# DLP.net
KiCad netlist of a schematic drawn in Altium Designer
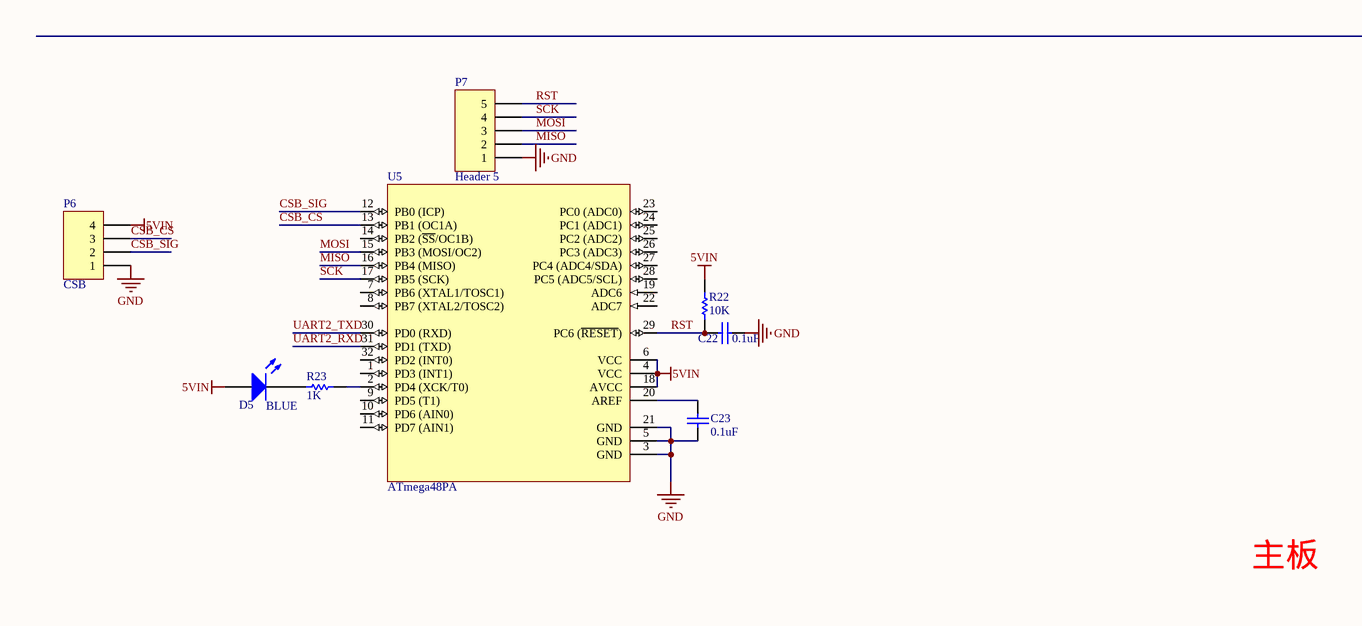
[diagram p0: DLP.SchDoc, top left]
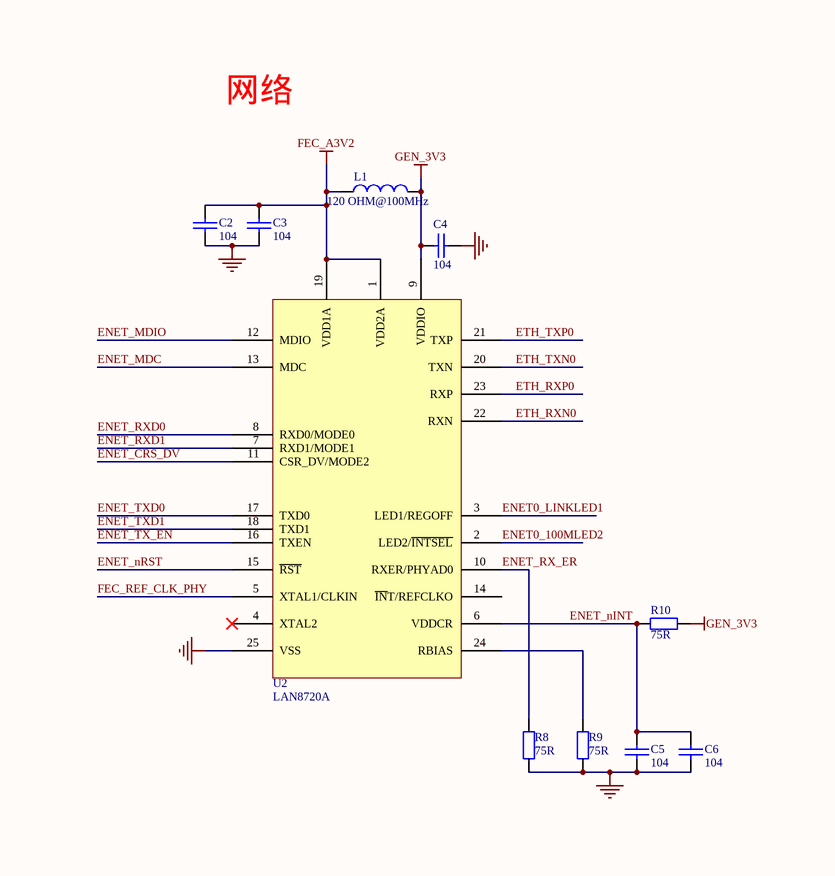
[diagram p1: DLP.SchDoc, top right]
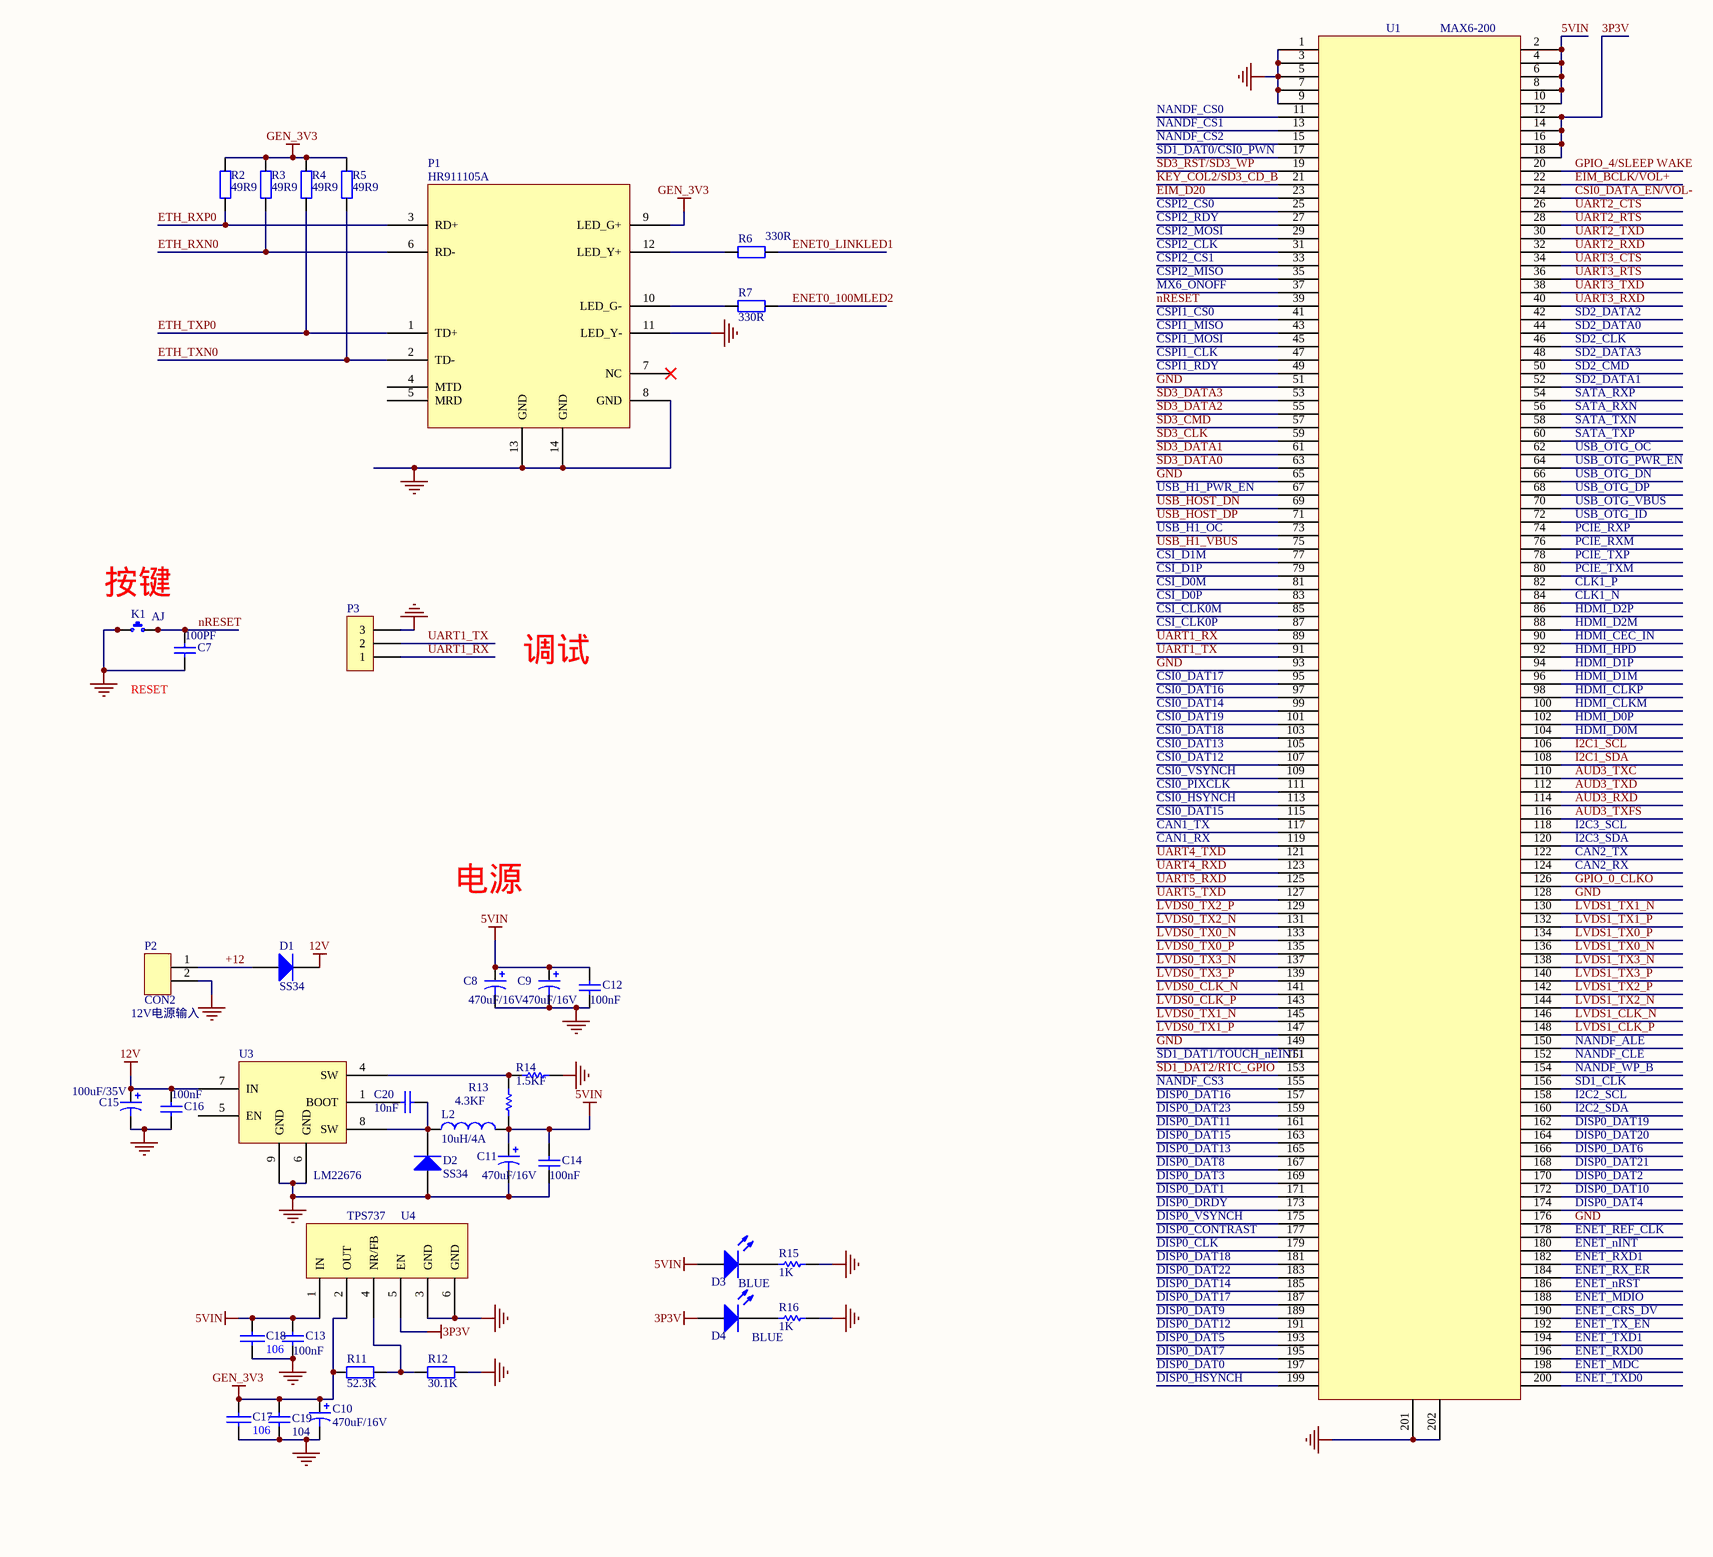
[diagram p2: DLP.SchDoc, bottom left]
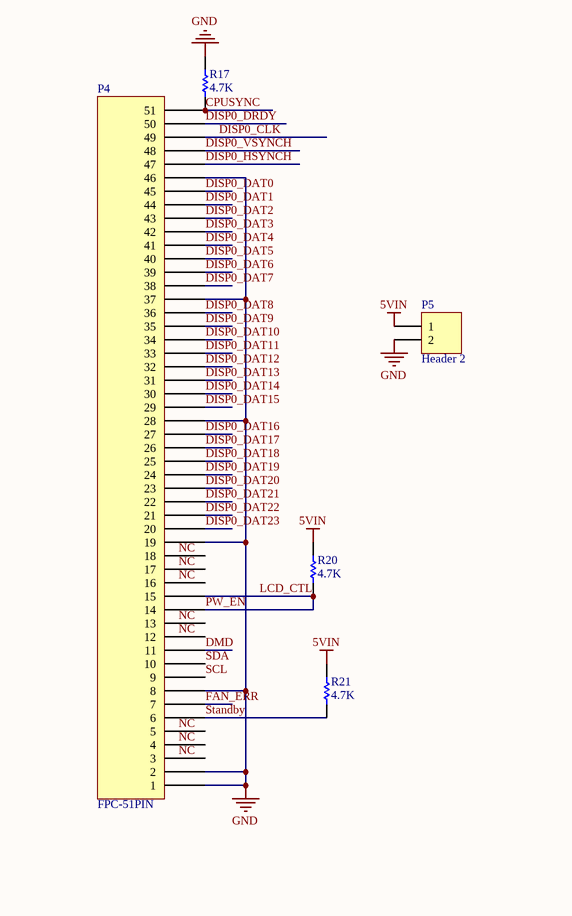
[diagram p3: DLP.SchDoc, bottom right]

(export (version "E")
  (design (tool "Eeschema 10.0.6"))
  (components
    (comp (ref "C2") (value "104") (footprint "0603C") (libsource (lib "*") (part "CAP")))
    (comp (ref "C3") (value "104") (footprint "0603C") (libsource (lib "*") (part "CAP")))
    (comp (ref "C4") (value "104") (footprint "0603C") (libsource (lib "*") (part "CAP")))
    (comp (ref "C5") (value "104") (footprint "0603C") (libsource (lib "*") (part "CAP")))
    (comp (ref "C6") (value "104") (footprint "0603C") (libsource (lib "*") (part "CAP")))
    (comp (ref "C7")
      (value "100PF")
      (footprint "0603C")
      (description "Capacitor")
      (libsource (lib "*") (part "Cap"))
    )
    (comp (ref "C8")
      (value "470uF/16V")
      (footprint "C8")
      (description "Polarized Capacitor (Radial)")
      (libsource (lib "*") (part "Cap Pol1"))
    )
    (comp (ref "C9")
      (value "470uF/16V")
      (footprint "C8")
      (description "Polarized Capacitor (Radial)")
      (libsource (lib "*") (part "Cap Pol1"))
    )
    (comp (ref "C10")
      (value "470uF/16V")
      (footprint "C8")
      (description "Polarized Capacitor (Radial)")
      (libsource (lib "*") (part "Cap Pol1"))
    )
    (comp (ref "C11")
      (value "470uF/16V")
      (footprint "C8")
      (description "Polarized Capacitor (Radial)")
      (libsource (lib "*") (part "Cap Pol1"))
    )
    (comp (ref "C12")
      (value "100nF")
      (footprint "0603C")
      (description "Capacitor")
      (libsource (lib "*") (part "Cap"))
    )
    (comp (ref "C13")
      (value "100nF")
      (footprint "0603C")
      (description "Capacitor")
      (libsource (lib "*") (part "Cap"))
    )
    (comp (ref "C14")
      (value "100nF")
      (footprint "0603C")
      (description "Capacitor")
      (libsource (lib "*") (part "Cap"))
    )
    (comp (ref "C15")
      (value "100uF/35V")
      (footprint "C8")
      (description "Polarized Capacitor (Radial)")
      (libsource (lib "*") (part "Cap Pol1"))
    )
    (comp (ref "C16")
      (value "100nF")
      (footprint "0603C")
      (description "Capacitor")
      (libsource (lib "*") (part "Cap"))
    )
    (comp (ref "C17") (value "106") (footprint "0603C") (libsource (lib "") (part "CAP_1")))
    (comp (ref "C18") (value "106") (footprint "0603C") (libsource (lib "") (part "CAP_1")))
    (comp (ref "C19")
      (value "104")
      (footprint "0603C")
      (fields (field (name "PUBLISHER") "Altium Limited"))
      (libsource (lib "*") (part "Cap"))
    )
    (comp (ref "C20")
      (value "10nF")
      (footprint "0603")
      (description "Capacitor")
      (libsource (lib "*") (part "Cap"))
    )
    (comp (ref "C22")
      (value "0.1uF")
      (footprint "0603")
      (description "Capacitor")
      (fields (field (name "Comment") "Cap") (field (name "PUBLISHER") "Altium Limited"))
      (libsource (lib "Miscellaneous Devices") (part "Cap"))
    )
    (comp (ref "C23")
      (value "0.1uF")
      (footprint "0603")
      (description "Capacitor")
      (fields (field (name "Comment") "Cap") (field (name "PUBLISHER") "Altium Limited"))
      (libsource (lib "Miscellaneous Devices") (part "Cap"))
    )
    (comp (ref "D1")
      (value "SS34")
      (footprint "SMB")
      (description "3 Amp Medium Power Silicon Rectifier Diode")
      (libsource (lib "*") (part "Diode 1N5408"))
    )
    (comp (ref "D2")
      (value "SS34")
      (footprint "SMB")
      (description "3 Amp Medium Power Silicon Rectifier Diode")
      (libsource (lib "*") (part "Diode 1N5408"))
    )
    (comp (ref "D3")
      (value "BLUE")
      (footprint "0603D")
      (description "Typical RED, GREEN, YELLOW, AMBER GaAs LED")
      (libsource (lib "*") (part "LED2"))
    )
    (comp (ref "D4")
      (value "BLUE")
      (footprint "0603D")
      (description "Typical RED, GREEN, YELLOW, AMBER GaAs LED")
      (libsource (lib "*") (part "LED2"))
    )
    (comp (ref "D5")
      (value "BLUE")
      (footprint "0603-LED")
      (description "Typical RED, GREEN, YELLOW, AMBER GaAs LED")
      (libsource (lib "*") (part "LED2"))
    )
    (comp (ref "K1") (value "AJ") (footprint "4*4*1.5") (libsource (lib "*") (part "KEY_1")))
    (comp (ref "L1")
      (value "120 OHM@100MHz")
      (footprint "0603")
      (description "Inductor")
      (libsource (lib "*") (part "Inductor"))
    )
    (comp (ref "L2")
      (value "10uH/4A")
      (footprint "8040")
      (description "Inductor")
      (libsource (lib "*") (part "Inductor"))
    )
    (comp (ref "P1") (value "HR911105A") (footprint "HR911105A") (libsource (lib "*") (part "HR911105A")))
    (comp (ref "P2") (value "CON2") (footprint "XH2.54-2P") (libsource (lib "*") (part "CON2")))
    (comp (ref "P3")
      (value "~")
      (footprint "HDR1X3")
      (description "Connector")
      (libsource (lib "*") (part "CON3"))
    )
    (comp (ref "P4")
      (value "FPC-51PIN")
      (footprint "FH26-51S-0.3SHW")
      (libsource (lib "TANK") (part "FPC-51PIN"))
    )
    (comp (ref "P5")
      (value "Header 2")
      (footprint "PH2.0-2P")
      (description "Header, 2-Pin")
      (fields (field (name "PUBLISHER") "Altium Limited"))
      (libsource (lib "Miscellaneous Connectors") (part "Header 2"))
    )
    (comp (ref "P6")
      (value "CSB")
      (footprint "HDR1X4")
      (description "Header, 4-Pin")
      (fields (field (name "PUBLISHER") "Altium Limited"))
      (libsource (lib "Miscellaneous Connectors") (part "Header 4"))
    )
    (comp (ref "P7")
      (value "Header 5")
      (footprint "HDR1X5")
      (description "Header, 5-Pin")
      (fields (field (name "PUBLISHER") "Altium Limited"))
      (libsource (lib "Miscellaneous Connectors") (part "Header 5"))
    )
    (comp (ref "R2") (value "49R9") (footprint "0603R") (libsource (lib "*") (part "RES")))
    (comp (ref "R3") (value "49R9") (footprint "0603R") (libsource (lib "*") (part "RES")))
    (comp (ref "R4") (value "49R9") (footprint "0603R") (libsource (lib "*") (part "RES")))
    (comp (ref "R5") (value "49R9") (footprint "0603") (libsource (lib "*") (part "RES")))
    (comp (ref "R6") (value "330R") (footprint "0603R") (libsource (lib "*") (part "RES")))
    (comp (ref "R7") (value "330R") (footprint "0603R") (libsource (lib "*") (part "RES")))
    (comp (ref "R8") (value "75R") (footprint "0603R") (libsource (lib "*") (part "RES")))
    (comp (ref "R9") (value "75R") (footprint "0603R") (libsource (lib "*") (part "RES")))
    (comp (ref "R10") (value "75R") (footprint "0603R") (libsource (lib "*") (part "RES")))
    (comp (ref "R11")
      (value "52.3K")
      (footprint "0603R")
      (description "Resistor")
      (fields (field (name "PUBLISHER") "Altium Limited"))
      (libsource (lib "*") (part "Res2"))
    )
    (comp (ref "R12")
      (value "30.1K")
      (footprint "0603R")
      (description "Resistor")
      (fields (field (name "PUBLISHER") "Altium Limited"))
      (libsource (lib "") (part "Res2_1"))
    )
    (comp (ref "R13")
      (value "4.3KF")
      (footprint "0603R")
      (description "Resistor")
      (libsource (lib "*") (part "Res1"))
    )
    (comp (ref "R14")
      (value "1.5KF")
      (footprint "0603R")
      (description "Resistor")
      (libsource (lib "*") (part "Res1"))
    )
    (comp (ref "R15")
      (value "1K")
      (footprint "0603R")
      (description "Resistor")
      (libsource (lib "*") (part "Res1"))
    )
    (comp (ref "R16")
      (value "1K")
      (footprint "0603R")
      (description "Resistor")
      (libsource (lib "*") (part "Res1"))
    )
    (comp (ref "R17")
      (value "4.7K")
      (footprint "0603")
      (description "Resistor")
      (fields (field (name "Comment") "Res1") (field (name "PUBLISHER") "Altium Limited"))
      (libsource (lib "Miscellaneous Devices") (part "Res1"))
    )
    (comp (ref "R20")
      (value "4.7K")
      (footprint "0603")
      (description "Resistor")
      (fields (field (name "Comment") "Res1") (field (name "PUBLISHER") "Altium Limited"))
      (libsource (lib "Miscellaneous Devices") (part "Res1"))
    )
    (comp (ref "R21")
      (value "4.7K")
      (footprint "0603")
      (description "Resistor")
      (fields (field (name "Comment") "Res1") (field (name "PUBLISHER") "Altium Limited"))
      (libsource (lib "Miscellaneous Devices") (part "Res1"))
    )
    (comp (ref "R22")
      (value "10K")
      (footprint "0603")
      (description "Resistor")
      (fields (field (name "Comment") "Res1") (field (name "PUBLISHER") "Altium Limited"))
      (libsource (lib "Miscellaneous Devices") (part "Res1"))
    )
    (comp (ref "R23")
      (value "1K")
      (footprint "0603")
      (description "Resistor")
      (libsource (lib "*") (part "Res1"))
    )
    (comp (ref "U1") (value "MAX6-200") (footprint "SO-DIMM 200") (libsource (lib "*") (part "MAX6-200")))
    (comp (ref "U2") (value "LAN8720A") (footprint "QFN24_4X4MM") (libsource (lib "*") (part "LAN8720A")))
    (comp (ref "U3") (value "LM22676") (footprint "SO-8HP") (libsource (lib "*") (part "LM22676")))
    (comp (ref "U4") (value "TPS737") (footprint "SOT223-6") (libsource (lib "*") (part "TPS737")))
    (comp (ref "U5")
      (value "ATmega48PA")
      (footprint "32A_M")
      (description "8-Bit AVR Microcontroller with 8K Bytes of In-System Programmable Flash Memory")
      (fields (field (name "PUBLISHER") "Altium Limited"))
      (libsource (lib "Atmel Microcontroller 8-Bit AVR") (part "ATmega8-16AC"))
    )
  )
  (nets
    (net (code "1") (name "/+12") (class "Default")
      (node (ref "D1") (pin "1") (pinfunction "A_1") (pintype "passive"))
      (node (ref "P2") (pin "1") (pinfunction "1_1") (pintype "passive"))
    )
    (net (code "2") (name "/AUD3_RXD") (class "Default") (node (ref "U1") (pin "114") (pintype "passive")))
    (net (code "3") (name "/AUD3_TXC") (class "Default") (node (ref "U1") (pin "110") (pintype "passive")))
    (net (code "4") (name "/AUD3_TXD") (class "Default") (node (ref "U1") (pin "112") (pintype "passive")))
    (net (code "5") (name "/AUD3_TXFS") (class "Default") (node (ref "U1") (pin "116") (pintype "passive")))
    (net (code "6") (name "/CAN1_RX") (class "Default") (node (ref "U1") (pin "119") (pintype "passive")))
    (net (code "7") (name "/CAN1_TX") (class "Default") (node (ref "U1") (pin "117") (pintype "passive")))
    (net (code "8") (name "/CAN2_RX") (class "Default") (node (ref "U1") (pin "124") (pintype "passive")))
    (net (code "9") (name "/CAN2_TX") (class "Default") (node (ref "U1") (pin "122") (pintype "passive")))
    (net (code "10") (name "/CLK1_N") (class "Default") (node (ref "U1") (pin "84") (pintype "passive")))
    (net (code "11") (name "/CLK1_P") (class "Default") (node (ref "U1") (pin "82") (pintype "passive")))
    (net (code "12") (name "/CPUSYNC") (class "Default")
      (node (ref "P4") (pin "51") (pinfunction "51_51") (pintype "passive"))
      (node (ref "R17") (pin "2") (pinfunction "2_2") (pintype "passive"))
    )
    (net (code "13") (name "/CSB_CS") (class "Default")
      (node (ref "P6") (pin "3") (pinfunction "3_3") (pintype "passive"))
      (node (ref "U5") (pin "13") (pinfunction "PB1_(OC1A)_13") (pintype "bidirectional"))
    )
    (net (code "14") (name "/CSB_SIG") (class "Default")
      (node (ref "P6") (pin "2") (pinfunction "2_2") (pintype "passive"))
      (node (ref "U5") (pin "12") (pinfunction "PB0_(ICP)_12") (pintype "bidirectional"))
    )
    (net (code "15") (name "/CSI0_DAT12") (class "Default") (node (ref "U1") (pin "107") (pintype "passive")))
    (net (code "16") (name "/CSI0_DAT13") (class "Default") (node (ref "U1") (pin "105") (pintype "passive")))
    (net (code "17") (name "/CSI0_DAT14") (class "Default") (node (ref "U1") (pin "99") (pintype "passive")))
    (net (code "18") (name "/CSI0_DAT15") (class "Default") (node (ref "U1") (pin "115") (pintype "passive")))
    (net (code "19") (name "/CSI0_DAT16") (class "Default") (node (ref "U1") (pin "97") (pintype "passive")))
    (net (code "20") (name "/CSI0_DAT17") (class "Default") (node (ref "U1") (pin "95") (pintype "passive")))
    (net (code "21") (name "/CSI0_DAT18") (class "Default") (node (ref "U1") (pin "103") (pintype "passive")))
    (net (code "22") (name "/CSI0_DAT19") (class "Default") (node (ref "U1") (pin "101") (pintype "passive")))
    (net (code "23") (name "/CSI0_DATA_EN{slash}VOL-") (class "Default")
      (node (ref "U1") (pin "24") (pintype "passive"))
    )
    (net (code "24") (name "/CSI0_HSYNCH") (class "Default")
      (node (ref "U1") (pin "113") (pintype "passive"))
    )
    (net (code "25") (name "/CSI0_PIXCLK") (class "Default")
      (node (ref "U1") (pin "111") (pintype "passive"))
    )
    (net (code "26") (name "/CSI0_VSYNCH") (class "Default")
      (node (ref "U1") (pin "109") (pintype "passive"))
    )
    (net (code "27") (name "/CSI_CLK0M") (class "Default") (node (ref "U1") (pin "85") (pintype "passive")))
    (net (code "28") (name "/CSI_CLK0P") (class "Default") (node (ref "U1") (pin "87") (pintype "passive")))
    (net (code "29") (name "/CSI_D0M") (class "Default") (node (ref "U1") (pin "81") (pintype "passive")))
    (net (code "30") (name "/CSI_D0P") (class "Default") (node (ref "U1") (pin "83") (pintype "passive")))
    (net (code "31") (name "/CSI_D1M") (class "Default") (node (ref "U1") (pin "77") (pintype "passive")))
    (net (code "32") (name "/CSI_D1P") (class "Default") (node (ref "U1") (pin "79") (pintype "passive")))
    (net (code "33") (name "/CSPI1_CLK") (class "Default") (node (ref "U1") (pin "47") (pintype "passive")))
    (net (code "34") (name "/CSPI1_CS0") (class "Default") (node (ref "U1") (pin "41") (pintype "passive")))
    (net (code "35") (name "/CSPI1_MISO") (class "Default") (node (ref "U1") (pin "43") (pintype "passive")))
    (net (code "36") (name "/CSPI1_MOSI") (class "Default") (node (ref "U1") (pin "45") (pintype "passive")))
    (net (code "37") (name "/CSPI1_RDY") (class "Default") (node (ref "U1") (pin "49") (pintype "passive")))
    (net (code "38") (name "/CSPI2_CLK") (class "Default") (node (ref "U1") (pin "31") (pintype "passive")))
    (net (code "39") (name "/CSPI2_CS0") (class "Default") (node (ref "U1") (pin "25") (pintype "passive")))
    (net (code "40") (name "/CSPI2_CS1") (class "Default") (node (ref "U1") (pin "33") (pintype "passive")))
    (net (code "41") (name "/CSPI2_MISO") (class "Default") (node (ref "U1") (pin "35") (pintype "passive")))
    (net (code "42") (name "/CSPI2_MOSI") (class "Default") (node (ref "U1") (pin "29") (pintype "passive")))
    (net (code "43") (name "/CSPI2_RDY") (class "Default") (node (ref "U1") (pin "27") (pintype "passive")))
    (net (code "44") (name "/DISP0_CLK") (class "Default")
      (node (ref "P4") (pin "49") (pinfunction "49_49") (pintype "passive"))
      (node (ref "U1") (pin "179") (pintype "passive"))
    )
    (net (code "45") (name "/DISP0_CONTRAST") (class "Default")
      (node (ref "U1") (pin "177") (pintype "passive"))
    )
    (net (code "46") (name "/DISP0_DAT0") (class "Default")
      (node (ref "P4") (pin "45") (pinfunction "45_45") (pintype "passive"))
      (node (ref "U1") (pin "197") (pintype "passive"))
    )
    (net (code "47") (name "/DISP0_DAT1") (class "Default")
      (node (ref "P4") (pin "44") (pinfunction "44_44") (pintype "passive"))
      (node (ref "U1") (pin "171") (pintype "passive"))
    )
    (net (code "48") (name "/DISP0_DAT2") (class "Default")
      (node (ref "P4") (pin "43") (pinfunction "43_43") (pintype "passive"))
      (node (ref "U1") (pin "170") (pintype "passive"))
    )
    (net (code "49") (name "/DISP0_DAT3") (class "Default")
      (node (ref "P4") (pin "42") (pinfunction "42_42") (pintype "passive"))
      (node (ref "U1") (pin "169") (pintype "passive"))
    )
    (net (code "50") (name "/DISP0_DAT4") (class "Default")
      (node (ref "P4") (pin "41") (pinfunction "41_41") (pintype "passive"))
      (node (ref "U1") (pin "174") (pintype "passive"))
    )
    (net (code "51") (name "/DISP0_DAT5") (class "Default")
      (node (ref "P4") (pin "40") (pinfunction "40_40") (pintype "passive"))
      (node (ref "U1") (pin "193") (pintype "passive"))
    )
    (net (code "52") (name "/DISP0_DAT6") (class "Default")
      (node (ref "P4") (pin "39") (pinfunction "39_39") (pintype "passive"))
      (node (ref "U1") (pin "166") (pintype "passive"))
    )
    (net (code "53") (name "/DISP0_DAT7") (class "Default")
      (node (ref "P4") (pin "38") (pinfunction "38_38") (pintype "passive"))
      (node (ref "U1") (pin "195") (pintype "passive"))
    )
    (net (code "54") (name "/DISP0_DAT8") (class "Default")
      (node (ref "P4") (pin "36") (pinfunction "36_36") (pintype "passive"))
      (node (ref "U1") (pin "167") (pintype "passive"))
    )
    (net (code "55") (name "/DISP0_DAT9") (class "Default")
      (node (ref "P4") (pin "35") (pinfunction "35_35") (pintype "passive"))
      (node (ref "U1") (pin "189") (pintype "passive"))
    )
    (net (code "56") (name "/DISP0_DAT10") (class "Default")
      (node (ref "P4") (pin "34") (pinfunction "34_34") (pintype "passive"))
      (node (ref "U1") (pin "172") (pintype "passive"))
    )
    (net (code "57") (name "/DISP0_DAT11") (class "Default")
      (node (ref "P4") (pin "33") (pinfunction "33_33") (pintype "passive"))
      (node (ref "U1") (pin "161") (pintype "passive"))
    )
    (net (code "58") (name "/DISP0_DAT12") (class "Default")
      (node (ref "P4") (pin "32") (pinfunction "32_32") (pintype "passive"))
      (node (ref "U1") (pin "191") (pintype "passive"))
    )
    (net (code "59") (name "/DISP0_DAT13") (class "Default")
      (node (ref "P4") (pin "31") (pinfunction "31_31") (pintype "passive"))
      (node (ref "U1") (pin "165") (pintype "passive"))
    )
    (net (code "60") (name "/DISP0_DAT14") (class "Default")
      (node (ref "P4") (pin "30") (pinfunction "30_30") (pintype "passive"))
      (node (ref "U1") (pin "185") (pintype "passive"))
    )
    (net (code "61") (name "/DISP0_DAT15") (class "Default")
      (node (ref "P4") (pin "29") (pinfunction "29_29") (pintype "passive"))
      (node (ref "U1") (pin "163") (pintype "passive"))
    )
    (net (code "62") (name "/DISP0_DAT16") (class "Default")
      (node (ref "P4") (pin "27") (pinfunction "27_27") (pintype "passive"))
      (node (ref "U1") (pin "157") (pintype "passive"))
    )
    (net (code "63") (name "/DISP0_DAT17") (class "Default")
      (node (ref "P4") (pin "26") (pinfunction "26_26") (pintype "passive"))
      (node (ref "U1") (pin "187") (pintype "passive"))
    )
    (net (code "64") (name "/DISP0_DAT18") (class "Default")
      (node (ref "P4") (pin "25") (pinfunction "25_25") (pintype "passive"))
      (node (ref "U1") (pin "181") (pintype "passive"))
    )
    (net (code "65") (name "/DISP0_DAT19") (class "Default")
      (node (ref "P4") (pin "24") (pinfunction "24_24") (pintype "passive"))
      (node (ref "U1") (pin "162") (pintype "passive"))
    )
    (net (code "66") (name "/DISP0_DAT20") (class "Default")
      (node (ref "P4") (pin "23") (pinfunction "23_23") (pintype "passive"))
      (node (ref "U1") (pin "164") (pintype "passive"))
    )
    (net (code "67") (name "/DISP0_DAT21") (class "Default")
      (node (ref "P4") (pin "22") (pinfunction "22_22") (pintype "passive"))
      (node (ref "U1") (pin "168") (pintype "passive"))
    )
    (net (code "68") (name "/DISP0_DAT22") (class "Default")
      (node (ref "P4") (pin "21") (pinfunction "21_21") (pintype "passive"))
      (node (ref "U1") (pin "183") (pintype "passive"))
    )
    (net (code "69") (name "/DISP0_DAT23") (class "Default")
      (node (ref "P4") (pin "20") (pinfunction "20_20") (pintype "passive"))
      (node (ref "U1") (pin "159") (pintype "passive"))
    )
    (net (code "70") (name "/DISP0_DRDY") (class "Default")
      (node (ref "P4") (pin "50") (pinfunction "50_50") (pintype "passive"))
      (node (ref "U1") (pin "173") (pintype "passive"))
    )
    (net (code "71") (name "/DISP0_HSYNCH") (class "Default")
      (node (ref "P4") (pin "47") (pinfunction "47_47") (pintype "passive"))
      (node (ref "U1") (pin "199") (pintype "passive"))
    )
    (net (code "72") (name "/DISP0_VSYNCH") (class "Default")
      (node (ref "P4") (pin "48") (pinfunction "48_48") (pintype "passive"))
      (node (ref "U1") (pin "175") (pintype "passive"))
    )
    (net (code "73") (name "/DMD") (class "Default")
      (node (ref "P4") (pin "11") (pinfunction "11_11") (pintype "passive"))
    )
    (net (code "74") (name "/EIM_BCLK{slash}VOL+") (class "Default")
      (node (ref "U1") (pin "22") (pintype "passive"))
    )
    (net (code "75") (name "/EIM_D20") (class "Default") (node (ref "U1") (pin "23") (pintype "passive")))
    (net (code "76") (name "/ENET0_100MLED2") (class "Default")
      (node (ref "R7") (pin "2") (pinfunction "2_2") (pintype "passive"))
      (node (ref "U2") (pin "2") (pinfunction "LED2/~{INTSEL}_2") (pintype "passive"))
    )
    (net (code "77") (name "/ENET0_LINKLED1") (class "Default")
      (node (ref "R6") (pin "2") (pinfunction "2_2") (pintype "passive"))
      (node (ref "U2") (pin "3") (pinfunction "LED1/REGOFF_3") (pintype "passive"))
    )
    (net (code "78") (name "/ENET_CRS_DV") (class "Default")
      (node (ref "U1") (pin "190") (pintype "passive"))
      (node (ref "U2") (pin "11") (pinfunction "CSR_DV/MODE2_11") (pintype "passive"))
    )
    (net (code "79") (name "/ENET_MDC") (class "Default")
      (node (ref "U1") (pin "198") (pintype "passive"))
      (node (ref "U2") (pin "13") (pinfunction "MDC_13") (pintype "passive"))
    )
    (net (code "80") (name "/ENET_MDIO") (class "Default")
      (node (ref "U1") (pin "188") (pintype "passive"))
      (node (ref "U2") (pin "12") (pinfunction "MDIO_12") (pintype "passive"))
    )
    (net (code "81") (name "/ENET_REF_CLK") (class "Default")
      (node (ref "U1") (pin "178") (pintype "passive"))
    )
    (net (code "82") (name "/ENET_RXD0") (class "Default")
      (node (ref "U1") (pin "196") (pintype "passive"))
      (node (ref "U2") (pin "8") (pinfunction "RXD0/MODE0_8") (pintype "passive"))
    )
    (net (code "83") (name "/ENET_RXD1") (class "Default")
      (node (ref "U1") (pin "182") (pintype "passive"))
      (node (ref "U2") (pin "7") (pinfunction "RXD1/MODE1_7") (pintype "passive"))
    )
    (net (code "84") (name "/ENET_RX_ER") (class "Default")
      (node (ref "R8") (pin "2") (pinfunction "2_2") (pintype "passive"))
      (node (ref "U1") (pin "184") (pintype "passive"))
      (node (ref "U2") (pin "10") (pinfunction "RXER/PHYAD0_10") (pintype "passive"))
    )
    (net (code "85") (name "/ENET_TXD0") (class "Default")
      (node (ref "U1") (pin "200") (pintype "passive"))
      (node (ref "U2") (pin "17") (pinfunction "TXD0_17") (pintype "passive"))
    )
    (net (code "86") (name "/ENET_TXD1") (class "Default")
      (node (ref "U1") (pin "194") (pintype "passive"))
      (node (ref "U2") (pin "18") (pinfunction "TXD1_18") (pintype "passive"))
    )
    (net (code "87") (name "/ENET_TX_EN") (class "Default")
      (node (ref "U1") (pin "192") (pintype "passive"))
      (node (ref "U2") (pin "16") (pinfunction "TXEN_16") (pintype "passive"))
    )
    (net (code "88") (name "/ENET_nINT") (class "Default")
      (node (ref "C5") (pin "1") (pintype "passive"))
      (node (ref "C6") (pin "1") (pintype "passive"))
      (node (ref "R10") (pin "2") (pinfunction "2_2") (pintype "passive"))
      (node (ref "U1") (pin "180") (pintype "passive"))
      (node (ref "U2") (pin "6") (pinfunction "VDDCR_6") (pintype "passive"))
    )
    (net (code "89") (name "/ENET_nRST") (class "Default")
      (node (ref "U1") (pin "186") (pintype "passive"))
      (node (ref "U2") (pin "15") (pinfunction "~{RST}_15") (pintype "passive"))
    )
    (net (code "90") (name "/ETH_RXN0") (class "Default")
      (node (ref "P1") (pin "6") (pinfunction "RD-_6") (pintype "passive"))
      (node (ref "R3") (pin "1") (pinfunction "1_1") (pintype "passive"))
      (node (ref "U2") (pin "22") (pinfunction "RXN_22") (pintype "passive"))
    )
    (net (code "91") (name "/ETH_RXP0") (class "Default")
      (node (ref "P1") (pin "3") (pinfunction "RD+_3") (pintype "passive"))
      (node (ref "R2") (pin "1") (pinfunction "1_1") (pintype "passive"))
      (node (ref "U2") (pin "23") (pinfunction "RXP_23") (pintype "passive"))
    )
    (net (code "92") (name "/ETH_TXN0") (class "Default")
      (node (ref "P1") (pin "2") (pinfunction "TD-_2") (pintype "passive"))
      (node (ref "R5") (pin "1") (pinfunction "1_1") (pintype "passive"))
      (node (ref "U2") (pin "20") (pinfunction "TXN_20") (pintype "passive"))
    )
    (net (code "93") (name "/ETH_TXP0") (class "Default")
      (node (ref "P1") (pin "1") (pinfunction "TD+_1") (pintype "passive"))
      (node (ref "R4") (pin "1") (pinfunction "1_1") (pintype "passive"))
      (node (ref "U2") (pin "21") (pinfunction "TXP_21") (pintype "passive"))
    )
    (net (code "94") (name "/FAN_ERR") (class "Default")
      (node (ref "P4") (pin "7") (pinfunction "7_7") (pintype "passive"))
    )
    (net (code "95") (name "/FEC_REF_CLK_PHY") (class "Default")
      (node (ref "U2") (pin "5") (pinfunction "XTAL1/CLKIN_5") (pintype "passive"))
    )
    (net (code "96") (name "/GPIO_0_CLKO") (class "Default")
      (node (ref "U1") (pin "126") (pintype "passive"))
    )
    (net (code "97") (name "/GPIO_4{slash}SLEEP WAKE") (class "Default")
      (node (ref "U1") (pin "20") (pintype "passive"))
    )
    (net (code "98") (name "/HDMI_CEC_IN") (class "Default") (node (ref "U1") (pin "90") (pintype "passive")))
    (net (code "99") (name "/HDMI_CLKM") (class "Default") (node (ref "U1") (pin "100") (pintype "passive")))
    (net (code "100") (name "/HDMI_CLKP") (class "Default") (node (ref "U1") (pin "98") (pintype "passive")))
    (net (code "101") (name "/HDMI_D0M") (class "Default") (node (ref "U1") (pin "104") (pintype "passive")))
    (net (code "102") (name "/HDMI_D0P") (class "Default") (node (ref "U1") (pin "102") (pintype "passive")))
    (net (code "103") (name "/HDMI_D1M") (class "Default") (node (ref "U1") (pin "96") (pintype "passive")))
    (net (code "104") (name "/HDMI_D1P") (class "Default") (node (ref "U1") (pin "94") (pintype "passive")))
    (net (code "105") (name "/HDMI_D2M") (class "Default") (node (ref "U1") (pin "88") (pintype "passive")))
    (net (code "106") (name "/HDMI_D2P") (class "Default") (node (ref "U1") (pin "86") (pintype "passive")))
    (net (code "107") (name "/HDMI_HPD") (class "Default") (node (ref "U1") (pin "92") (pintype "passive")))
    (net (code "108") (name "/I2C1_SCL") (class "Default") (node (ref "U1") (pin "106") (pintype "passive")))
    (net (code "109") (name "/I2C1_SDA") (class "Default") (node (ref "U1") (pin "108") (pintype "passive")))
    (net (code "110") (name "/I2C2_SCL") (class "Default") (node (ref "U1") (pin "158") (pintype "passive")))
    (net (code "111") (name "/I2C2_SDA") (class "Default") (node (ref "U1") (pin "160") (pintype "passive")))
    (net (code "112") (name "/I2C3_SCL") (class "Default") (node (ref "U1") (pin "118") (pintype "passive")))
    (net (code "113") (name "/I2C3_SDA") (class "Default") (node (ref "U1") (pin "120") (pintype "passive")))
    (net (code "114") (name "/KEY_COL2{slash}SD3_CD_B") (class "Default")
      (node (ref "U1") (pin "21") (pintype "passive"))
    )
    (net (code "115") (name "/LCD_CTL") (class "Default")
      (node (ref "P4") (pin "14") (pinfunction "14_14") (pintype "passive"))
      (node (ref "P4") (pin "15") (pinfunction "15_15") (pintype "passive"))
      (node (ref "R20") (pin "2") (pinfunction "2_2") (pintype "passive"))
    )
    (net (code "116") (name "/LVDS0_CLK_N") (class "Default")
      (node (ref "U1") (pin "141") (pintype "passive"))
    )
    (net (code "117") (name "/LVDS0_CLK_P") (class "Default")
      (node (ref "U1") (pin "143") (pintype "passive"))
    )
    (net (code "118") (name "/LVDS0_TX0_N") (class "Default")
      (node (ref "U1") (pin "133") (pintype "passive"))
    )
    (net (code "119") (name "/LVDS0_TX0_P") (class "Default")
      (node (ref "U1") (pin "135") (pintype "passive"))
    )
    (net (code "120") (name "/LVDS0_TX1_N") (class "Default")
      (node (ref "U1") (pin "145") (pintype "passive"))
    )
    (net (code "121") (name "/LVDS0_TX1_P") (class "Default")
      (node (ref "U1") (pin "147") (pintype "passive"))
    )
    (net (code "122") (name "/LVDS0_TX2_N") (class "Default")
      (node (ref "U1") (pin "131") (pintype "passive"))
    )
    (net (code "123") (name "/LVDS0_TX2_P") (class "Default")
      (node (ref "U1") (pin "129") (pintype "passive"))
    )
    (net (code "124") (name "/LVDS0_TX3_N") (class "Default")
      (node (ref "U1") (pin "137") (pintype "passive"))
    )
    (net (code "125") (name "/LVDS0_TX3_P") (class "Default")
      (node (ref "U1") (pin "139") (pintype "passive"))
    )
    (net (code "126") (name "/LVDS1_CLK_N") (class "Default")
      (node (ref "U1") (pin "146") (pintype "passive"))
    )
    (net (code "127") (name "/LVDS1_CLK_P") (class "Default")
      (node (ref "U1") (pin "148") (pintype "passive"))
    )
    (net (code "128") (name "/LVDS1_TX0_N") (class "Default")
      (node (ref "U1") (pin "136") (pintype "passive"))
    )
    (net (code "129") (name "/LVDS1_TX0_P") (class "Default")
      (node (ref "U1") (pin "134") (pintype "passive"))
    )
    (net (code "130") (name "/LVDS1_TX1_N") (class "Default")
      (node (ref "U1") (pin "130") (pintype "passive"))
    )
    (net (code "131") (name "/LVDS1_TX1_P") (class "Default")
      (node (ref "U1") (pin "132") (pintype "passive"))
    )
    (net (code "132") (name "/LVDS1_TX2_N") (class "Default")
      (node (ref "U1") (pin "144") (pintype "passive"))
    )
    (net (code "133") (name "/LVDS1_TX2_P") (class "Default")
      (node (ref "U1") (pin "142") (pintype "passive"))
    )
    (net (code "134") (name "/LVDS1_TX3_N") (class "Default")
      (node (ref "U1") (pin "138") (pintype "passive"))
    )
    (net (code "135") (name "/LVDS1_TX3_P") (class "Default")
      (node (ref "U1") (pin "140") (pintype "passive"))
    )
    (net (code "136") (name "/MISO") (class "Default")
      (node (ref "P7") (pin "2") (pinfunction "2_2") (pintype "passive"))
      (node (ref "U5") (pin "16") (pinfunction "PB4_(MISO)_16") (pintype "bidirectional"))
    )
    (net (code "137") (name "/MOSI") (class "Default")
      (node (ref "P7") (pin "3") (pinfunction "3_3") (pintype "passive"))
      (node (ref "U5") (pin "15") (pinfunction "PB3_(MOSI/OC2)_15") (pintype "bidirectional"))
    )
    (net (code "138") (name "/MX6_ONOFF") (class "Default") (node (ref "U1") (pin "37") (pintype "passive")))
    (net (code "139") (name "/NANDF_ALE") (class "Default") (node (ref "U1") (pin "150") (pintype "passive")))
    (net (code "140") (name "/NANDF_CLE") (class "Default") (node (ref "U1") (pin "152") (pintype "passive")))
    (net (code "141") (name "/NANDF_CS0") (class "Default") (node (ref "U1") (pin "11") (pintype "passive")))
    (net (code "142") (name "/NANDF_CS1") (class "Default") (node (ref "U1") (pin "13") (pintype "passive")))
    (net (code "143") (name "/NANDF_CS2") (class "Default") (node (ref "U1") (pin "15") (pintype "passive")))
    (net (code "144") (name "/NANDF_CS3") (class "Default") (node (ref "U1") (pin "155") (pintype "passive")))
    (net (code "145") (name "/NANDF_WP_B") (class "Default")
      (node (ref "U1") (pin "154") (pintype "passive"))
    )
    (net (code "147") (name "/PCIE_RXM") (class "Default") (node (ref "U1") (pin "76") (pintype "passive")))
    (net (code "148") (name "/PCIE_RXP") (class "Default") (node (ref "U1") (pin "74") (pintype "passive")))
    (net (code "149") (name "/PCIE_TXM") (class "Default") (node (ref "U1") (pin "80") (pintype "passive")))
    (net (code "150") (name "/PCIE_TXP") (class "Default") (node (ref "U1") (pin "78") (pintype "passive")))
    (net (code "151") (name "/RST") (class "Default")
      (node (ref "C22") (pin "1") (pinfunction "1_1") (pintype "passive"))
      (node (ref "P7") (pin "5") (pinfunction "5_5") (pintype "passive"))
      (node (ref "R22") (pin "1") (pinfunction "1_1") (pintype "passive"))
      (node (ref "U5") (pin "29") (pinfunction "PC6_(~{RESET})_29") (pintype "bidirectional"))
    )
    (net (code "152") (name "/SATA_RXN") (class "Default") (node (ref "U1") (pin "56") (pintype "passive")))
    (net (code "153") (name "/SATA_RXP") (class "Default") (node (ref "U1") (pin "54") (pintype "passive")))
    (net (code "154") (name "/SATA_TXN") (class "Default") (node (ref "U1") (pin "58") (pintype "passive")))
    (net (code "155") (name "/SATA_TXP") (class "Default") (node (ref "U1") (pin "60") (pintype "passive")))
    (net (code "156") (name "/SCK") (class "Default")
      (node (ref "P7") (pin "4") (pinfunction "4_4") (pintype "passive"))
      (node (ref "U5") (pin "17") (pinfunction "PB5_(SCK)_17") (pintype "bidirectional"))
    )
    (net (code "157") (name "/SCL") (class "Default")
      (node (ref "P4") (pin "9") (pinfunction "9_9") (pintype "passive"))
    )
    (net (code "158") (name "/SD1_CLK") (class "Default") (node (ref "U1") (pin "156") (pintype "passive")))
    (net (code "159") (name "/SD1_DAT0{slash}CSI0_PWN") (class "Default")
      (node (ref "U1") (pin "17") (pintype "passive"))
    )
    (net (code "160") (name "/SD1_DAT1{slash}TOUCH_nEINT1") (class "Default")
      (node (ref "U1") (pin "151") (pintype "passive"))
    )
    (net (code "161") (name "/SD1_DAT2{slash}RTC_GPIO") (class "Default")
      (node (ref "U1") (pin "153") (pintype "passive"))
    )
    (net (code "162") (name "/SD2_CLK") (class "Default") (node (ref "U1") (pin "46") (pintype "passive")))
    (net (code "163") (name "/SD2_CMD") (class "Default") (node (ref "U1") (pin "50") (pintype "passive")))
    (net (code "164") (name "/SD2_DATA0") (class "Default") (node (ref "U1") (pin "44") (pintype "passive")))
    (net (code "165") (name "/SD2_DATA1") (class "Default") (node (ref "U1") (pin "52") (pintype "passive")))
    (net (code "166") (name "/SD2_DATA2") (class "Default") (node (ref "U1") (pin "42") (pintype "passive")))
    (net (code "167") (name "/SD2_DATA3") (class "Default") (node (ref "U1") (pin "48") (pintype "passive")))
    (net (code "168") (name "/SD3_CLK") (class "Default") (node (ref "U1") (pin "59") (pintype "passive")))
    (net (code "169") (name "/SD3_CMD") (class "Default") (node (ref "U1") (pin "57") (pintype "passive")))
    (net (code "170") (name "/SD3_DATA0") (class "Default") (node (ref "U1") (pin "63") (pintype "passive")))
    (net (code "171") (name "/SD3_DATA1") (class "Default") (node (ref "U1") (pin "61") (pintype "passive")))
    (net (code "172") (name "/SD3_DATA2") (class "Default") (node (ref "U1") (pin "55") (pintype "passive")))
    (net (code "173") (name "/SD3_DATA3") (class "Default") (node (ref "U1") (pin "53") (pintype "passive")))
    (net (code "174") (name "/SD3_RST{slash}SD3_WP") (class "Default")
      (node (ref "U1") (pin "19") (pintype "passive"))
    )
    (net (code "175") (name "/SDA") (class "Default")
      (node (ref "P4") (pin "10") (pinfunction "10_10") (pintype "passive"))
    )
    (net (code "176") (name "/Standby") (class "Default")
      (node (ref "P4") (pin "6") (pinfunction "6_6") (pintype "passive"))
      (node (ref "R21") (pin "2") (pinfunction "2_2") (pintype "passive"))
    )
    (net (code "177") (name "/UART1_RX") (class "Default")
      (node (ref "P3") (pin "1") (pinfunction "1_1") (pintype "passive"))
      (node (ref "U1") (pin "89") (pintype "passive"))
    )
    (net (code "178") (name "/UART1_TX") (class "Default")
      (node (ref "P3") (pin "2") (pinfunction "2_2") (pintype "passive"))
      (node (ref "U1") (pin "91") (pintype "passive"))
    )
    (net (code "179") (name "/UART2_CTS") (class "Default") (node (ref "U1") (pin "26") (pintype "passive")))
    (net (code "180") (name "/UART2_RTS") (class "Default") (node (ref "U1") (pin "28") (pintype "passive")))
    (net (code "181") (name "/UART2_RXD") (class "Default")
      (node (ref "U1") (pin "32") (pintype "passive"))
      (node (ref "U5") (pin "31") (pinfunction "PD1_(TXD)_31") (pintype "bidirectional"))
    )
    (net (code "182") (name "/UART2_TXD") (class "Default")
      (node (ref "U1") (pin "30") (pintype "passive"))
      (node (ref "U5") (pin "30") (pinfunction "PD0_(RXD)_30") (pintype "bidirectional"))
    )
    (net (code "183") (name "/UART3_CTS") (class "Default") (node (ref "U1") (pin "34") (pintype "passive")))
    (net (code "184") (name "/UART3_RTS") (class "Default") (node (ref "U1") (pin "36") (pintype "passive")))
    (net (code "185") (name "/UART3_RXD") (class "Default") (node (ref "U1") (pin "40") (pintype "passive")))
    (net (code "186") (name "/UART3_TXD") (class "Default") (node (ref "U1") (pin "38") (pintype "passive")))
    (net (code "187") (name "/UART4_RXD") (class "Default") (node (ref "U1") (pin "123") (pintype "passive")))
    (net (code "188") (name "/UART4_TXD") (class "Default") (node (ref "U1") (pin "121") (pintype "passive")))
    (net (code "189") (name "/UART5_RXD") (class "Default") (node (ref "U1") (pin "125") (pintype "passive")))
    (net (code "190") (name "/UART5_TXD") (class "Default") (node (ref "U1") (pin "127") (pintype "passive")))
    (net (code "191") (name "/USB_H1_OC") (class "Default") (node (ref "U1") (pin "73") (pintype "passive")))
    (net (code "192") (name "/USB_H1_PWR_EN") (class "Default")
      (node (ref "U1") (pin "67") (pintype "passive"))
    )
    (net (code "193") (name "/USB_H1_VBUS") (class "Default")
      (node (ref "U1") (pin "75") (pintype "passive"))
    )
    (net (code "194") (name "/USB_HOST_DN") (class "Default")
      (node (ref "U1") (pin "69") (pintype "passive"))
    )
    (net (code "195") (name "/USB_HOST_DP") (class "Default")
      (node (ref "U1") (pin "71") (pintype "passive"))
    )
    (net (code "196") (name "/USB_OTG_DN") (class "Default") (node (ref "U1") (pin "66") (pintype "passive")))
    (net (code "197") (name "/USB_OTG_DP") (class "Default") (node (ref "U1") (pin "68") (pintype "passive")))
    (net (code "198") (name "/USB_OTG_ID") (class "Default") (node (ref "U1") (pin "72") (pintype "passive")))
    (net (code "199") (name "/USB_OTG_OC") (class "Default") (node (ref "U1") (pin "62") (pintype "passive")))
    (net (code "200") (name "/USB_OTG_PWR_EN") (class "Default")
      (node (ref "U1") (pin "64") (pintype "passive"))
    )
    (net (code "201") (name "/USB_OTG_VBUS") (class "Default")
      (node (ref "U1") (pin "70") (pintype "passive"))
    )
    (net (code "202") (name "/nRESET") (class "Default")
      (node (ref "C7") (pin "2") (pinfunction "2_2") (pintype "passive"))
      (node (ref "K1") (pin "3") (pintype "passive"))
      (node (ref "K1") (pin "4") (pintype "passive"))
      (node (ref "U1") (pin "39") (pintype "passive"))
    )
    (net (code "203") (name "3P3V") (class "Default")
      (node (ref "D4") (pin "1") (pinfunction "A_1") (pintype "passive"))
      (node (ref "U1") (pin "12") (pintype "passive"))
      (node (ref "U1") (pin "14") (pintype "passive"))
      (node (ref "U1") (pin "16") (pintype "passive"))
      (node (ref "U1") (pin "18") (pintype "passive"))
      (node (ref "U4") (pin "5") (pinfunction "EN_5") (pintype "passive"))
    )
    (net (code "204") (name "5VIN") (class "Default")
      (node (ref "C11") (pin "1") (pinfunction "1_1") (pintype "passive"))
      (node (ref "C12") (pin "2") (pinfunction "2_2") (pintype "passive"))
      (node (ref "C13") (pin "2") (pinfunction "2_2") (pintype "passive"))
      (node (ref "C14") (pin "2") (pinfunction "2_2") (pintype "passive"))
      (node (ref "C18") (pin "1") (pintype "passive"))
      (node (ref "C8") (pin "1") (pinfunction "1_1") (pintype "passive"))
      (node (ref "C9") (pin "1") (pinfunction "1_1") (pintype "passive"))
      (node (ref "D3") (pin "1") (pinfunction "A_1") (pintype "passive"))
      (node (ref "D5") (pin "1") (pinfunction "A_1") (pintype "passive"))
      (node (ref "L2") (pin "2") (pinfunction "2_2") (pintype "passive"))
      (node (ref "P5") (pin "1") (pinfunction "1_1") (pintype "passive"))
      (node (ref "P6") (pin "4") (pinfunction "4_4") (pintype "passive"))
      (node (ref "R13") (pin "2") (pinfunction "2_2") (pintype "passive"))
      (node (ref "R20") (pin "1") (pinfunction "1_1") (pintype "passive"))
      (node (ref "R21") (pin "1") (pinfunction "1_1") (pintype "passive"))
      (node (ref "R22") (pin "2") (pinfunction "2_2") (pintype "passive"))
      (node (ref "U1") (pin "10") (pintype "passive"))
      (node (ref "U1") (pin "2") (pintype "passive"))
      (node (ref "U1") (pin "4") (pintype "passive"))
      (node (ref "U1") (pin "6") (pintype "passive"))
      (node (ref "U1") (pin "8") (pintype "passive"))
      (node (ref "U4") (pin "1") (pinfunction "IN_1") (pintype "passive"))
      (node (ref "U5") (pin "18") (pinfunction "AVCC_18") (pintype "power_in"))
      (node (ref "U5") (pin "4") (pinfunction "VCC_4") (pintype "power_in"))
      (node (ref "U5") (pin "6") (pinfunction "VCC_6") (pintype "power_in"))
    )
    (net (code "205") (name "12V") (class "Default")
      (node (ref "C15") (pin "1") (pinfunction "1_1") (pintype "passive"))
      (node (ref "C16") (pin "2") (pinfunction "2_2") (pintype "passive"))
      (node (ref "D1") (pin "2") (pinfunction "K_2") (pintype "passive"))
      (node (ref "U3") (pin "7") (pinfunction "IN_7") (pintype "passive"))
    )
    (net (code "206") (name "FEC_A3V2") (class "Default")
      (node (ref "C2") (pin "1") (pintype "passive"))
      (node (ref "C3") (pin "1") (pintype "passive"))
      (node (ref "L1") (pin "1") (pinfunction "1_1") (pintype "passive"))
      (node (ref "U2") (pin "1") (pinfunction "VDD2A_1") (pintype "passive"))
      (node (ref "U2") (pin "19") (pinfunction "VDD1A_19") (pintype "passive"))
    )
    (net (code "207") (name "GEN_3V3") (class "Default")
      (node (ref "C10") (pin "1") (pinfunction "1_1") (pintype "passive"))
      (node (ref "C17") (pin "1") (pintype "passive"))
      (node (ref "C19") (pin "2") (pinfunction "2_2") (pintype "passive"))
      (node (ref "C4") (pin "2") (pintype "passive"))
      (node (ref "L1") (pin "2") (pinfunction "2_2") (pintype "passive"))
      (node (ref "P1") (pin "9") (pinfunction "LED_G+_9") (pintype "passive"))
      (node (ref "R10") (pin "1") (pinfunction "1_1") (pintype "passive"))
      (node (ref "R11") (pin "2") (pinfunction "2_2") (pintype "passive"))
      (node (ref "R2") (pin "2") (pinfunction "2_2") (pintype "passive"))
      (node (ref "R3") (pin "2") (pinfunction "2_2") (pintype "passive"))
      (node (ref "R4") (pin "2") (pinfunction "2_2") (pintype "passive"))
      (node (ref "R5") (pin "2") (pinfunction "2_2") (pintype "passive"))
      (node (ref "U2") (pin "9") (pinfunction "VDDIO_9") (pintype "passive"))
      (node (ref "U4") (pin "2") (pinfunction "OUT_2") (pintype "passive"))
    )
    (net (code "208") (name "GND") (class "Default")
      (node (ref "C10") (pin "2") (pinfunction "2_2") (pintype "passive"))
      (node (ref "C11") (pin "2") (pinfunction "2_2") (pintype "passive"))
      (node (ref "C12") (pin "1") (pinfunction "1_1") (pintype "passive"))
      (node (ref "C13") (pin "1") (pinfunction "1_1") (pintype "passive"))
      (node (ref "C14") (pin "1") (pinfunction "1_1") (pintype "passive"))
      (node (ref "C15") (pin "2") (pinfunction "2_2") (pintype "passive"))
      (node (ref "C16") (pin "1") (pinfunction "1_1") (pintype "passive"))
      (node (ref "C17") (pin "2") (pintype "passive"))
      (node (ref "C18") (pin "2") (pintype "passive"))
      (node (ref "C19") (pin "1") (pinfunction "1_1") (pintype "passive"))
      (node (ref "C2") (pin "2") (pintype "passive"))
      (node (ref "C22") (pin "2") (pinfunction "2_2") (pintype "passive"))
      (node (ref "C23") (pin "2") (pinfunction "2_2") (pintype "passive"))
      (node (ref "C3") (pin "2") (pintype "passive"))
      (node (ref "C4") (pin "1") (pintype "passive"))
      (node (ref "C5") (pin "2") (pintype "passive"))
      (node (ref "C6") (pin "2") (pintype "passive"))
      (node (ref "C7") (pin "1") (pinfunction "1_1") (pintype "passive"))
      (node (ref "C8") (pin "2") (pinfunction "2_2") (pintype "passive"))
      (node (ref "C9") (pin "2") (pinfunction "2_2") (pintype "passive"))
      (node (ref "D2") (pin "1") (pinfunction "A_1") (pintype "passive"))
      (node (ref "K1") (pin "1") (pintype "passive"))
      (node (ref "K1") (pin "2") (pintype "passive"))
      (node (ref "P1") (pin "11") (pinfunction "LED_Y-_11") (pintype "passive"))
      (node (ref "P1") (pin "13") (pinfunction "GND_13") (pintype "passive"))
      (node (ref "P1") (pin "14") (pinfunction "GND_14") (pintype "passive"))
      (node (ref "P1") (pin "8") (pinfunction "GND_8") (pintype "passive"))
      (node (ref "P2") (pin "2") (pinfunction "2_2") (pintype "passive"))
      (node (ref "P3") (pin "3") (pinfunction "3_3") (pintype "passive"))
      (node (ref "P4") (pin "1") (pinfunction "1_1") (pintype "passive"))
      (node (ref "P4") (pin "19") (pinfunction "19_19") (pintype "passive"))
      (node (ref "P4") (pin "2") (pinfunction "2_2") (pintype "passive"))
      (node (ref "P4") (pin "28") (pinfunction "28_28") (pintype "passive"))
      (node (ref "P4") (pin "37") (pinfunction "37_37") (pintype "passive"))
      (node (ref "P4") (pin "46") (pinfunction "46_46") (pintype "passive"))
      (node (ref "P4") (pin "8") (pinfunction "8_8") (pintype "passive"))
      (node (ref "P5") (pin "2") (pinfunction "2_2") (pintype "passive"))
      (node (ref "P6") (pin "1") (pinfunction "1_1") (pintype "passive"))
      (node (ref "P7") (pin "1") (pinfunction "1_1") (pintype "passive"))
      (node (ref "R12") (pin "2") (pinfunction "2_2") (pintype "passive"))
      (node (ref "R14") (pin "2") (pinfunction "2_2") (pintype "passive"))
      (node (ref "R15") (pin "1") (pinfunction "1_1") (pintype "passive"))
      (node (ref "R16") (pin "1") (pinfunction "1_1") (pintype "passive"))
      (node (ref "R17") (pin "1") (pinfunction "1_1") (pintype "passive"))
      (node (ref "R8") (pin "1") (pinfunction "1_1") (pintype "passive"))
      (node (ref "R9") (pin "1") (pinfunction "1_1") (pintype "passive"))
      (node (ref "U1") (pin "1") (pintype "passive"))
      (node (ref "U1") (pin "128") (pintype "passive"))
      (node (ref "U1") (pin "149") (pintype "passive"))
      (node (ref "U1") (pin "176") (pintype "passive"))
      (node (ref "U1") (pin "201") (pintype "passive"))
      (node (ref "U1") (pin "202") (pintype "passive"))
      (node (ref "U1") (pin "3") (pintype "passive"))
      (node (ref "U1") (pin "5") (pintype "passive"))
      (node (ref "U1") (pin "51") (pintype "passive"))
      (node (ref "U1") (pin "65") (pintype "passive"))
      (node (ref "U1") (pin "7") (pintype "passive"))
      (node (ref "U1") (pin "9") (pintype "passive"))
      (node (ref "U1") (pin "93") (pintype "passive"))
      (node (ref "U2") (pin "25") (pinfunction "VSS_25") (pintype "passive"))
      (node (ref "U3") (pin "6") (pinfunction "GND_6") (pintype "passive"))
      (node (ref "U3") (pin "9") (pinfunction "GND_9") (pintype "passive"))
      (node (ref "U4") (pin "3") (pinfunction "GND_3") (pintype "passive"))
      (node (ref "U4") (pin "6") (pinfunction "GND_6") (pintype "passive"))
      (node (ref "U5") (pin "21") (pinfunction "GND_21") (pintype "power_in"))
      (node (ref "U5") (pin "3") (pinfunction "GND_3") (pintype "power_in"))
      (node (ref "U5") (pin "5") (pinfunction "GND_5") (pintype "power_in"))
    )
    (net (code "209") (name "Net-(D2-K)") (class "Default")
      (node (ref "C20") (pin "1") (pinfunction "1_1") (pintype "passive"))
      (node (ref "D2") (pin "2") (pinfunction "K_2") (pintype "passive"))
      (node (ref "L2") (pin "1") (pinfunction "1_1") (pintype "passive"))
      (node (ref "U3") (pin "8") (pinfunction "SW_8") (pintype "passive"))
    )
    (net (code "210") (name "Net-(D3-K)") (class "Default")
      (node (ref "D3") (pin "2") (pinfunction "K_2") (pintype "passive"))
      (node (ref "R15") (pin "2") (pinfunction "2_2") (pintype "passive"))
    )
    (net (code "211") (name "Net-(D4-K)") (class "Default")
      (node (ref "D4") (pin "2") (pinfunction "K_2") (pintype "passive"))
      (node (ref "R16") (pin "2") (pinfunction "2_2") (pintype "passive"))
    )
    (net (code "212") (name "Net-(D5-K)") (class "Default")
      (node (ref "D5") (pin "2") (pinfunction "K_2") (pintype "passive"))
      (node (ref "R23") (pin "2") (pinfunction "2_2") (pintype "passive"))
    )
    (net (code "213") (name "Net-(P1-LED_G-)") (class "Default")
      (node (ref "P1") (pin "10") (pinfunction "LED_G-_10") (pintype "passive"))
      (node (ref "R7") (pin "1") (pinfunction "1_1") (pintype "passive"))
    )
    (net (code "214") (name "Net-(P1-LED_Y+)") (class "Default")
      (node (ref "P1") (pin "12") (pinfunction "LED_Y+_12") (pintype "passive"))
      (node (ref "R6") (pin "1") (pinfunction "1_1") (pintype "passive"))
    )
    (net (code "215") (name "Net-(R13-Pad1)") (class "Default")
      (node (ref "R13") (pin "1") (pinfunction "1_1") (pintype "passive"))
      (node (ref "R14") (pin "1") (pinfunction "1_1") (pintype "passive"))
      (node (ref "U3") (pin "4") (pinfunction "SW_4") (pintype "passive"))
    )
    (net (code "216") (name "Net-(U2-RBIAS)") (class "Default")
      (node (ref "R9") (pin "2") (pinfunction "2_2") (pintype "passive"))
      (node (ref "U2") (pin "24") (pinfunction "RBIAS_24") (pintype "passive"))
    )
    (net (code "217") (name "Net-(U3-BOOT)") (class "Default")
      (node (ref "C20") (pin "2") (pinfunction "2_2") (pintype "passive"))
      (node (ref "U3") (pin "1") (pinfunction "BOOT_1") (pintype "passive"))
    )
    (net (code "218") (name "Net-(U4-NR{slash}FB)") (class "Default")
      (node (ref "R11") (pin "1") (pinfunction "1_1") (pintype "passive"))
      (node (ref "R12") (pin "1") (pinfunction "1_1") (pintype "passive"))
      (node (ref "U4") (pin "4") (pinfunction "NR/FB_4") (pintype "passive"))
    )
    (net (code "219") (name "Net-(U5-AREF)") (class "Default")
      (node (ref "C23") (pin "1") (pinfunction "1_1") (pintype "passive"))
      (node (ref "U5") (pin "20") (pinfunction "AREF_20") (pintype "passive"))
    )
    (net (code "220") (name "Net-(U5-PD4_(XCK{slash}T0))") (class "Default")
      (node (ref "R23") (pin "1") (pinfunction "1_1") (pintype "passive"))
      (node (ref "U5") (pin "2") (pinfunction "PD4_(XCK/T0)_2") (pintype "bidirectional"))
    )
    (net (code "221") (name "unconnected-(P1-MRD-Pad5)") (class "Default")
      (node (ref "P1") (pin "5") (pinfunction "MRD_5") (pintype "passive"))
    )
    (net (code "222") (name "unconnected-(P1-MTD-Pad4)") (class "Default")
      (node (ref "P1") (pin "4") (pinfunction "MTD_4") (pintype "passive"))
    )
    (net (code "223") (name "unconnected-(P1-NC-Pad7)") (class "Default")
      (node (ref "P1") (pin "7") (pinfunction "NC_7") (pintype "passive+no_connect"))
    )
    (net (code "224") (name "unconnected-(P4-Pad3)") (class "Default")
      (node (ref "P4") (pin "3") (pinfunction "3_3") (pintype "passive"))
    )
    (net (code "225") (name "unconnected-(P4-Pad4)") (class "Default")
      (node (ref "P4") (pin "4") (pinfunction "4_4") (pintype "passive"))
    )
    (net (code "226") (name "unconnected-(P4-Pad5)") (class "Default")
      (node (ref "P4") (pin "5") (pinfunction "5_5") (pintype "passive"))
    )
    (net (code "227") (name "unconnected-(P4-Pad12)") (class "Default")
      (node (ref "P4") (pin "12") (pinfunction "12_12") (pintype "passive"))
    )
    (net (code "228") (name "unconnected-(P4-Pad13)") (class "Default")
      (node (ref "P4") (pin "13") (pinfunction "13_13") (pintype "passive"))
    )
    (net (code "229") (name "unconnected-(P4-Pad16)") (class "Default")
      (node (ref "P4") (pin "16") (pinfunction "16_16") (pintype "passive"))
    )
    (net (code "230") (name "unconnected-(P4-Pad17)") (class "Default")
      (node (ref "P4") (pin "17") (pinfunction "17_17") (pintype "passive"))
    )
    (net (code "231") (name "unconnected-(P4-Pad18)") (class "Default")
      (node (ref "P4") (pin "18") (pinfunction "18_18") (pintype "passive"))
    )
    (net (code "232") (name "unconnected-(U2-XTAL2-Pad4)") (class "Default")
      (node (ref "U2") (pin "4") (pinfunction "XTAL2_4") (pintype "passive+no_connect"))
    )
    (net (code "233") (name "unconnected-(U2-~{IN}T{slash}REFCLKO-Pad14)") (class "Default")
      (node (ref "U2") (pin "14") (pinfunction "~{IN}T/REFCLKO_14") (pintype "passive"))
    )
    (net (code "234") (name "unconnected-(U3-EN-Pad5)") (class "Default")
      (node (ref "U3") (pin "5") (pinfunction "EN_5") (pintype "passive"))
    )
    (net (code "235") (name "unconnected-(U5-ADC6-Pad19)") (class "Default")
      (node (ref "U5") (pin "19") (pinfunction "ADC6_19") (pintype "input"))
    )
    (net (code "236") (name "unconnected-(U5-ADC7-Pad22)") (class "Default")
      (node (ref "U5") (pin "22") (pinfunction "ADC7_22") (pintype "input"))
    )
    (net (code "237") (name "unconnected-(U5-PB2_(~{SS}{slash}OC1B)-Pad14)") (class "Default")
      (node (ref "U5") (pin "14") (pinfunction "PB2_(~{SS}/OC1B)_14") (pintype "bidirectional"))
    )
    (net (code "238") (name "unconnected-(U5-PB6_(XTAL1{slash}TOSC1)-Pad7)") (class "Default")
      (node (ref "U5") (pin "7") (pinfunction "PB6_(XTAL1/TOSC1)_7") (pintype "bidirectional"))
    )
    (net (code "239") (name "unconnected-(U5-PB7_(XTAL2{slash}TOSC2)-Pad8)") (class "Default")
      (node (ref "U5") (pin "8") (pinfunction "PB7_(XTAL2/TOSC2)_8") (pintype "bidirectional"))
    )
    (net (code "240") (name "unconnected-(U5-PC0_(ADC0)-Pad23)") (class "Default")
      (node (ref "U5") (pin "23") (pinfunction "PC0_(ADC0)_23") (pintype "bidirectional"))
    )
    (net (code "241") (name "unconnected-(U5-PC1_(ADC1)-Pad24)") (class "Default")
      (node (ref "U5") (pin "24") (pinfunction "PC1_(ADC1)_24") (pintype "bidirectional"))
    )
    (net (code "242") (name "unconnected-(U5-PC2_(ADC2)-Pad25)") (class "Default")
      (node (ref "U5") (pin "25") (pinfunction "PC2_(ADC2)_25") (pintype "bidirectional"))
    )
    (net (code "243") (name "unconnected-(U5-PC3_(ADC3)-Pad26)") (class "Default")
      (node (ref "U5") (pin "26") (pinfunction "PC3_(ADC3)_26") (pintype "bidirectional"))
    )
    (net (code "244") (name "unconnected-(U5-PC4_(ADC4{slash}SDA)-Pad27)") (class "Default")
      (node (ref "U5") (pin "27") (pinfunction "PC4_(ADC4/SDA)_27") (pintype "bidirectional"))
    )
    (net (code "245") (name "unconnected-(U5-PC5_(ADC5{slash}SCL)-Pad28)") (class "Default")
      (node (ref "U5") (pin "28") (pinfunction "PC5_(ADC5/SCL)_28") (pintype "bidirectional"))
    )
    (net (code "246") (name "unconnected-(U5-PD2_(INT0)-Pad32)") (class "Default")
      (node (ref "U5") (pin "32") (pinfunction "PD2_(INT0)_32") (pintype "bidirectional"))
    )
    (net (code "247") (name "unconnected-(U5-PD3_(INT1)-Pad1)") (class "Default")
      (node (ref "U5") (pin "1") (pinfunction "PD3_(INT1)_1") (pintype "bidirectional"))
    )
    (net (code "248") (name "unconnected-(U5-PD5_(T1)-Pad9)") (class "Default")
      (node (ref "U5") (pin "9") (pinfunction "PD5_(T1)_9") (pintype "bidirectional"))
    )
    (net (code "249") (name "unconnected-(U5-PD6_(AIN0)-Pad10)") (class "Default")
      (node (ref "U5") (pin "10") (pinfunction "PD6_(AIN0)_10") (pintype "bidirectional"))
    )
    (net (code "250") (name "unconnected-(U5-PD7_(AIN1)-Pad11)") (class "Default")
      (node (ref "U5") (pin "11") (pinfunction "PD7_(AIN1)_11") (pintype "bidirectional"))
    )
  )
)
